# PSU1.net
KiCad netlist of a schematic drawn in Altium Designer
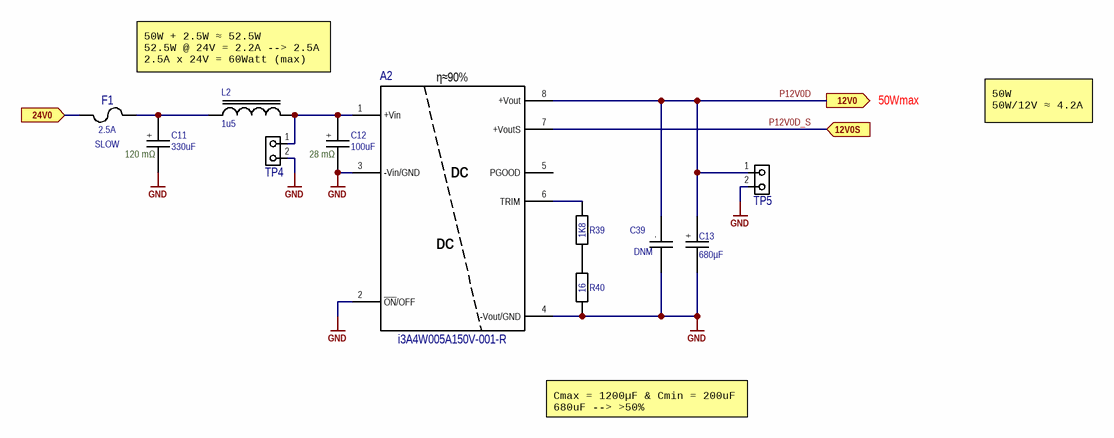
[diagram p0: PSU1.SchDoc]

(export (version "E")
  (design (tool "Eeschema 10.0.6"))
  (components
    (comp (ref "A2")
      (value "A")
      (footprint "I3A-POSETIVE")
      (description "DC DC CONVERTER 5-30V 135W")
      (fields
        (field (name "02. DISTRIBUTOR PART NUMBER") "285-2719-ND")
        (field (name "07. MANUFACTURER  PART NUMBER") "I3A4W005A150V-001-R")
        (field (name "NICNAME") "i3A4W005A150V-001-R")
        (field (name "EFFICIENCY") "η≈90%")
        (field (name "13. CREATED DATE/NAME") "AUG 2018 / Hören")
      )
      (libsource (lib "tom") (part "i3A4W005A150V-001-R"))
    )
    (comp (ref "C11")
      (value "330uF")
      (footprint "SMD-CAP-ALU-G")
      (description "CAP ALUM 330UF 20% 50V SMD")
      (fields
        (field (name "TOLERANCE") "±20%")
        (field (name "ESR") "120 mΩ")
        (field (name "02. DISTRIBUTOR PART NUMBER") "PCE5026DKR-ND")
        (field (name "13. CREATED DATE/NAME") "AUG2018/Hören")
      )
      (libsource (lib "chickenfood") (part "C+"))
    )
    (comp (ref "C12")
      (value "100uF")
      (footprint "SMD-CAP-ALU-G")
      (description "CAP ALUM POLY HYB 100UF 50V SMD")
      (fields
        (field (name "TOLERANCE") "±20%")
        (field (name "ESR") "28 mΩ")
        (field (name "02. DISTRIBUTOR PART NUMBER") "P15442DKR-ND")
        (field (name "13. CREATED DATE/NAME") "AUG2018/Hören")
      )
      (libsource (lib "chickenfood") (part "C+"))
    )
    (comp (ref "C13")
      (value "680µF")
      (footprint "CAP_EL_KE0")
      (description "CAP ALUM 680UF 20% 50V SMD")
      (fields (field (name "TOLERANCE") "±20%") (field (name "02. DISTRIBUTOR PART NUMBER") "PCE3465CT-ND"))
      (libsource (lib "chickenfood") (part "C+"))
    )
    (comp (ref "C39")
      (value "DNM")
      (footprint "C0402 Reflow")
      (description "CAP CER 0.1UF 16V X7R 0402")
      (fields
        (field (name "TOLERANCE") "±5%")
        (field (name "02. DISTRIBUTOR PART NUMBER") "399-7761-6-ND")
        (field (name "13. CREATED DATE/NAME") "AUG2018/Hören")
      )
      (libsource (lib "chickenfood") (part "C"))
    )
    (comp (ref "F1")
      (value "2.5A")
      (footprint "OMNI-Fuse")
      (description "FUSE BRD MNT 2.5A 125VAC/VDC SMD")
      (fields
        (field (name "02. DISTRIBUTOR PART NUMBER") "F1306DKR-ND")
        (field (name "07. MANUFACTURER  PART NUMBER") "015402.5DRT")
        (field (name "SPEED") "SLOW")
        (field (name "13. CREATED DATE/NAME") "AUG 2018 / Hören")
      )
      (libsource (lib "tom") (part "Fuse"))
    )
    (comp (ref "L2")
      (value "L")
      (footprint "XAL4020")
      (description "Fixed Inductors 1.5uH Shld 20% 7.5A 23.6mOhms AECQ2")
      (fields
        (field (name "02. DISTRIBUTOR PART NUMBER") "994-XAL4020-152MEC")
        (field (name "07. MANUFACTURER  PART NUMBER") "XAL4020-152MEC")
        (field (name "INDUCTANCE") "1u5")
      )
      (libsource (lib "PCB-Tester-Board-V1") (part "INDUCTOR"))
    )
    (comp (ref "R39")
      (value "1K8")
      (footprint "R0603 Reflow")
      (description "RES SMD 1.8K OHM 1% 1/16W 0402")
      (fields
        (field (name "TOLERANCE") "±1%")
        (field (name "02. DISTRIBUTOR PART NUMBER") "311-1.80KLRCT-ND")
        (field (name "13. CREATED DATE/NAME") "AUG2018/Hören")
      )
      (libsource (lib "chickenfood") (part "R"))
    )
    (comp (ref "R40")
      (value "16")
      (footprint "R0603 Reflow")
      (description "RES SMD 16 OHM 1% 1/10W 0603")
      (fields
        (field (name "TOLERANCE") "±1%")
        (field (name "02. DISTRIBUTOR PART NUMBER") "311-16.0HRDKR-ND")
        (field (name "13. CREATED DATE/NAME") "AUG2018/Hören")
      )
      (libsource (lib "chickenfood") (part "R"))
    )
    (comp (ref "TP4")
      (value "TP")
      (footprint "DualTestpoint 100mils")
      (description "Dual testpoint, pitch 2.54mm")
      (fields
        (field (name "02. DISTRIBUTOR PART NUMBER") "HMTSW-103-07-G-S-240")
        (field (name "13. CREATED DATE/NAME") "AUG2018/Hören")
      )
      (libsource (lib "PCB-Tester-Board-V1") (part "DualTestpoint 100mils"))
    )
    (comp (ref "TP5")
      (value "TP")
      (footprint "DualTestpoint 100mils")
      (description "Dual testpoint, pitch 2.54mm")
      (fields
        (field (name "02. DISTRIBUTOR PART NUMBER") "HMTSW-103-07-G-S-240")
        (field (name "13. CREATED DATE/NAME") "AUG2018/Hören")
      )
      (libsource (lib "PCB-Tester-Board-V1") (part "DualTestpoint 100mils"))
    )
  )
  (nets
    (net (code "1") (name "/24V0") (class "Default")
      (node (ref "F1") (pin "1") (pinfunction "1_1") (pintype "passive"))
    )
    (net (code "2") (name "/P12V0D") (class "Default")
      (node (ref "A2") (pin "8") (pinfunction "+Vout_8") (pintype "passive"))
      (node (ref "C13") (pin "1") (pinfunction "1_1") (pintype "passive"))
      (node (ref "C39") (pin "1") (pinfunction "1_1") (pintype "passive"))
      (node (ref "TP5") (pin "1") (pinfunction "1_1") (pintype "passive"))
    )
    (net (code "3") (name "/P12V0D_S") (class "Default")
      (node (ref "A2") (pin "7") (pinfunction "+VoutS_7") (pintype "passive"))
    )
    (net (code "4") (name "GND") (class "Default")
      (node (ref "A2") (pin "2") (pinfunction "~{ON}/OFF_2") (pintype "passive"))
      (node (ref "A2") (pin "3") (pinfunction "-Vin/GND_3") (pintype "passive"))
      (node (ref "A2") (pin "4") (pinfunction "-Vout/GND_4") (pintype "passive"))
      (node (ref "C11") (pin "2") (pinfunction "2_2") (pintype "passive"))
      (node (ref "C12") (pin "2") (pinfunction "2_2") (pintype "passive"))
      (node (ref "C13") (pin "2") (pinfunction "2_2") (pintype "passive"))
      (node (ref "C39") (pin "2") (pinfunction "2_2") (pintype "passive"))
      (node (ref "R40") (pin "1") (pinfunction "1_1") (pintype "passive"))
      (node (ref "TP4") (pin "2") (pinfunction "2_2") (pintype "passive"))
      (node (ref "TP5") (pin "2") (pinfunction "2_2") (pintype "passive"))
    )
    (net (code "5") (name "Net-(A2-+Vin)") (class "Default")
      (node (ref "A2") (pin "1") (pinfunction "+Vin_1") (pintype "passive"))
      (node (ref "C12") (pin "1") (pinfunction "1_1") (pintype "passive"))
      (node (ref "L2") (pin "1") (pinfunction "1_1") (pintype "passive"))
      (node (ref "TP4") (pin "1") (pinfunction "1_1") (pintype "passive"))
    )
    (net (code "6") (name "Net-(A2-TRIM)") (class "Default")
      (node (ref "A2") (pin "6") (pinfunction "TRIM_6") (pintype "passive"))
      (node (ref "R39") (pin "2") (pinfunction "2_2") (pintype "passive"))
    )
    (net (code "7") (name "Net-(C11-Pad1)") (class "Default")
      (node (ref "C11") (pin "1") (pinfunction "1_1") (pintype "passive"))
      (node (ref "F1") (pin "2") (pinfunction "2_2") (pintype "passive"))
      (node (ref "L2") (pin "2") (pinfunction "2_2") (pintype "passive"))
    )
    (net (code "8") (name "Net-(R39-Pad1)") (class "Default")
      (node (ref "R39") (pin "1") (pinfunction "1_1") (pintype "passive"))
      (node (ref "R40") (pin "2") (pinfunction "2_2") (pintype "passive"))
    )
    (net (code "9") (name "unconnected-(A2-PGOOD-Pad5)") (class "Default")
      (node (ref "A2") (pin "5") (pinfunction "PGOOD_5") (pintype "passive"))
    )
  )
)
